# esp8266-breakout.net
KiCad netlist of a schematic drawn in EAGLE
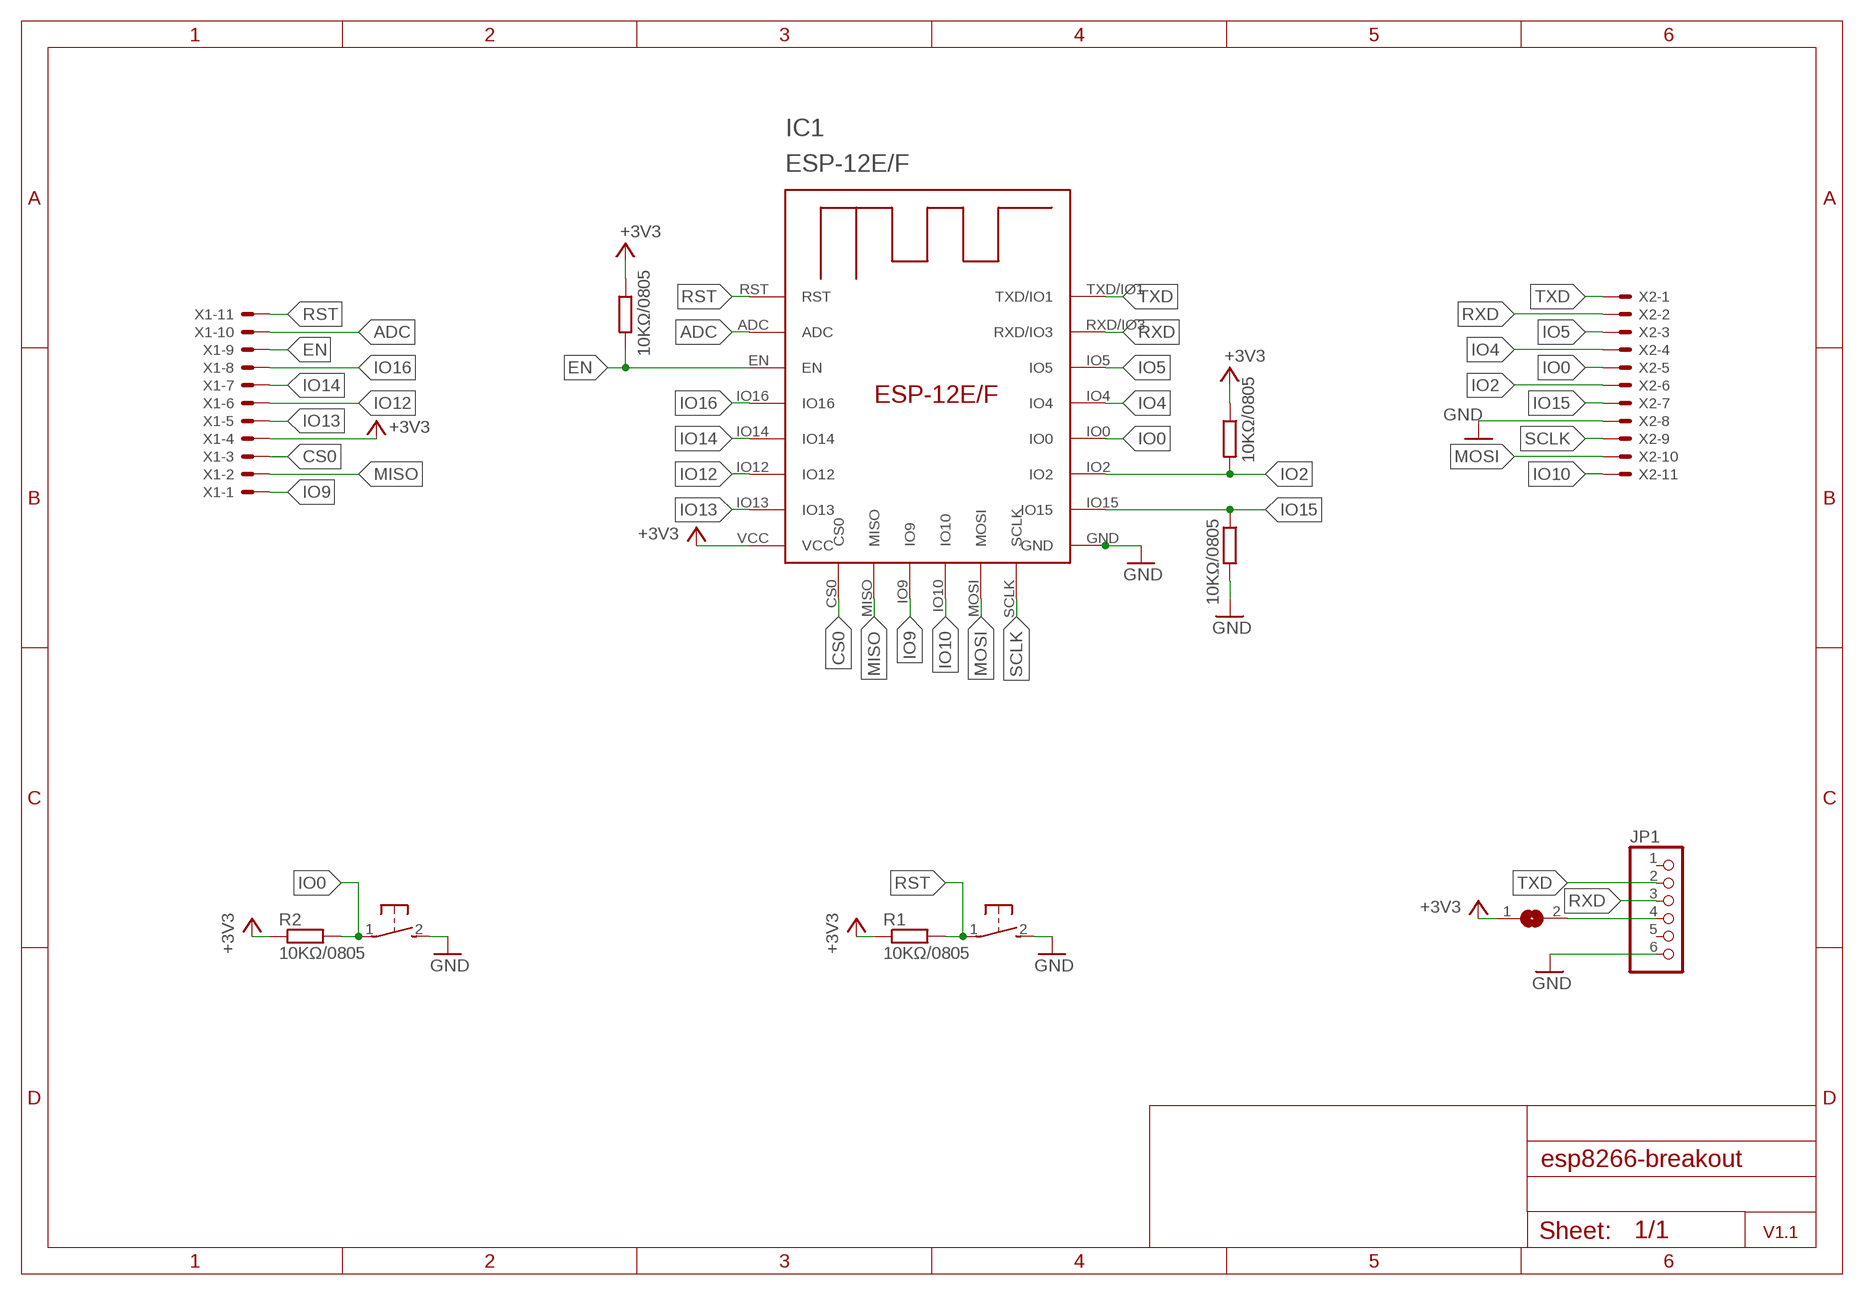
[diagram p0: schematic, sheet 1]

(export (version "E")
  (design (tool "Eeschema 10.0.6"))
  (components
    (comp (ref "IC1")
      (value "ESP-12E/F")
      (footprint "eagle-import:ESP-12E")
      (libsource (lib "eagle-import") (part "ESP-12E/F"))
    )
    (comp (ref "JP1")
      (value "PINHD-1X6B")
      (footprint "eagle-import:1X06-BIG")
      (libsource (lib "eagle-import") (part "PINHD-1X6B"))
    )
    (comp (ref "R1")
      (value "10KΩ/0805")
      (footprint "eagle-import:R0805")
      (libsource (lib "eagle-import") (part "R-EU_R0805"))
    )
    (comp (ref "R2")
      (value "10KΩ/0805")
      (footprint "eagle-import:R0805")
      (libsource (lib "eagle-import") (part "R-EU_R0805"))
    )
    (comp (ref "R3")
      (value "10KΩ/0805")
      (footprint "eagle-import:R0805")
      (libsource (lib "eagle-import") (part "R-EU_R0805"))
    )
    (comp (ref "R4")
      (value "10KΩ/0805")
      (footprint "eagle-import:R0805")
      (libsource (lib "eagle-import") (part "R-EU_R0805"))
    )
    (comp (ref "R5")
      (value "10KΩ/0805")
      (footprint "eagle-import:R0805")
      (libsource (lib "eagle-import") (part "R-EU_R0805"))
    )
    (comp (ref "S1")
      (value "DTSM-3")
      (footprint "eagle-import:DTSM-3")
      (libsource (lib "eagle-import") (part "DTSM-3"))
    )
    (comp (ref "S2")
      (value "DTSM-3")
      (footprint "eagle-import:DTSM-3")
      (libsource (lib "eagle-import") (part "DTSM-3"))
    )
    (comp (ref "SJ1") (value "SJ") (footprint "eagle-import:SJ") (libsource (lib "eagle-import") (part "SJ")))
    (comp (ref "X1")
      (value "JST-XH-11-PIN-ROUND-PAD")
      (footprint "eagle-import:JST-XH-11-PACKAGE-ROUND-PAD")
      (libsource (lib "eagle-import") (part "JST-XH-11-PIN-ROUND-PAD"))
    )
    (comp (ref "X2")
      (value "JST-XH-11-PIN-ROUND-PAD")
      (footprint "eagle-import:JST-XH-11-PACKAGE-ROUND-PAD")
      (libsource (lib "eagle-import") (part "JST-XH-11-PIN-ROUND-PAD"))
    )
  )
  (nets
    (net (code "1") (name "+3V3") (class "Default")
      (node (ref "IC1") (pin "VCC") (pinfunction "VCC_VCC") (pintype "power_in"))
      (node (ref "R1") (pin "1") (pinfunction "1_1") (pintype "passive"))
      (node (ref "R2") (pin "1") (pinfunction "1_1") (pintype "passive"))
      (node (ref "R4") (pin "1") (pinfunction "1_1") (pintype "passive"))
      (node (ref "R5") (pin "1") (pinfunction "1_1") (pintype "passive"))
      (node (ref "SJ1") (pin "1") (pinfunction "1_1") (pintype "passive"))
      (node (ref "X1") (pin "4") (pinfunction "S_4") (pintype "passive"))
    )
    (net (code "2") (name "ADC") (class "Default")
      (node (ref "IC1") (pin "ADC") (pinfunction "ADC_ADC") (pintype "bidirectional"))
      (node (ref "X1") (pin "10") (pinfunction "S_10") (pintype "passive"))
    )
    (net (code "3") (name "CS0") (class "Default")
      (node (ref "IC1") (pin "CS0") (pinfunction "CS0_CS0") (pintype "bidirectional"))
      (node (ref "X1") (pin "3") (pinfunction "S_3") (pintype "passive"))
    )
    (net (code "4") (name "EN") (class "Default")
      (node (ref "IC1") (pin "EN") (pinfunction "EN_EN") (pintype "bidirectional"))
      (node (ref "R5") (pin "2") (pinfunction "2_2") (pintype "passive"))
      (node (ref "X1") (pin "9") (pinfunction "S_9") (pintype "passive"))
    )
    (net (code "5") (name "GND") (class "Default")
      (node (ref "IC1") (pin "GND") (pinfunction "GND_GND") (pintype "power_in"))
      (node (ref "JP1") (pin "6") (pinfunction "6_6") (pintype "passive"))
      (node (ref "R3") (pin "2") (pinfunction "2_2") (pintype "passive"))
      (node (ref "S1") (pin "2") (pinfunction "2_2") (pintype "passive"))
      (node (ref "S2") (pin "2") (pinfunction "2_2") (pintype "passive"))
      (node (ref "X2") (pin "8") (pinfunction "S_8") (pintype "passive"))
    )
    (net (code "6") (name "IO0") (class "Default")
      (node (ref "IC1") (pin "IO0") (pinfunction "IO0_IO0") (pintype "bidirectional"))
      (node (ref "R2") (pin "2") (pinfunction "2_2") (pintype "passive"))
      (node (ref "S2") (pin "1") (pinfunction "1_1") (pintype "passive"))
      (node (ref "X2") (pin "5") (pinfunction "S_5") (pintype "passive"))
    )
    (net (code "7") (name "IO2") (class "Default")
      (node (ref "IC1") (pin "IO2") (pinfunction "IO2_IO2") (pintype "bidirectional"))
      (node (ref "R4") (pin "2") (pinfunction "2_2") (pintype "passive"))
      (node (ref "X2") (pin "6") (pinfunction "S_6") (pintype "passive"))
    )
    (net (code "8") (name "IO4") (class "Default")
      (node (ref "IC1") (pin "IO4") (pinfunction "IO4_IO4") (pintype "bidirectional"))
      (node (ref "X2") (pin "4") (pinfunction "S_4") (pintype "passive"))
    )
    (net (code "9") (name "IO5") (class "Default")
      (node (ref "IC1") (pin "IO5") (pinfunction "IO5_IO5") (pintype "bidirectional"))
      (node (ref "X2") (pin "3") (pinfunction "S_3") (pintype "passive"))
    )
    (net (code "10") (name "IO9") (class "Default")
      (node (ref "IC1") (pin "IO9") (pinfunction "IO9_IO9") (pintype "bidirectional"))
      (node (ref "X1") (pin "1") (pinfunction "S_1") (pintype "passive"))
    )
    (net (code "11") (name "IO10") (class "Default")
      (node (ref "IC1") (pin "IO10") (pinfunction "IO10_IO10") (pintype "bidirectional"))
      (node (ref "X2") (pin "11") (pinfunction "S_11") (pintype "passive"))
    )
    (net (code "12") (name "IO12") (class "Default")
      (node (ref "IC1") (pin "IO12") (pinfunction "IO12_IO12") (pintype "bidirectional"))
      (node (ref "X1") (pin "6") (pinfunction "S_6") (pintype "passive"))
    )
    (net (code "13") (name "IO13") (class "Default")
      (node (ref "IC1") (pin "IO13") (pinfunction "IO13_IO13") (pintype "bidirectional"))
      (node (ref "X1") (pin "5") (pinfunction "S_5") (pintype "passive"))
    )
    (net (code "14") (name "IO14") (class "Default")
      (node (ref "IC1") (pin "IO14") (pinfunction "IO14_IO14") (pintype "bidirectional"))
      (node (ref "X1") (pin "7") (pinfunction "S_7") (pintype "passive"))
    )
    (net (code "15") (name "IO15") (class "Default")
      (node (ref "IC1") (pin "IO15") (pinfunction "IO15_IO15") (pintype "bidirectional"))
      (node (ref "R3") (pin "1") (pinfunction "1_1") (pintype "passive"))
      (node (ref "X2") (pin "7") (pinfunction "S_7") (pintype "passive"))
    )
    (net (code "16") (name "IO16") (class "Default")
      (node (ref "IC1") (pin "IO16") (pinfunction "IO16_IO16") (pintype "bidirectional"))
      (node (ref "X1") (pin "8") (pinfunction "S_8") (pintype "passive"))
    )
    (net (code "17") (name "MISO") (class "Default")
      (node (ref "IC1") (pin "MISO") (pinfunction "MISO_MISO") (pintype "bidirectional"))
      (node (ref "X1") (pin "2") (pinfunction "S_2") (pintype "passive"))
    )
    (net (code "18") (name "MOSI") (class "Default")
      (node (ref "IC1") (pin "MOSI") (pinfunction "MOSI_MOSI") (pintype "bidirectional"))
      (node (ref "X2") (pin "10") (pinfunction "S_10") (pintype "passive"))
    )
    (net (code "19") (name "Net-(JP1-Pad4)") (class "Default")
      (node (ref "JP1") (pin "4") (pinfunction "4_4") (pintype "passive"))
      (node (ref "SJ1") (pin "2") (pinfunction "2_2") (pintype "passive"))
    )
    (net (code "20") (name "RST") (class "Default")
      (node (ref "IC1") (pin "RST") (pinfunction "RST_RST") (pintype "input"))
      (node (ref "R1") (pin "2") (pinfunction "2_2") (pintype "passive"))
      (node (ref "S1") (pin "1") (pinfunction "1_1") (pintype "passive"))
      (node (ref "X1") (pin "11") (pinfunction "S_11") (pintype "passive"))
    )
    (net (code "21") (name "RXD") (class "Default")
      (node (ref "IC1") (pin "RXD/IO3") (pinfunction "RXD/IO3_RXD/IO3") (pintype "bidirectional"))
      (node (ref "JP1") (pin "3") (pinfunction "3_3") (pintype "passive"))
      (node (ref "X2") (pin "2") (pinfunction "S_2") (pintype "passive"))
    )
    (net (code "22") (name "SCLK") (class "Default")
      (node (ref "IC1") (pin "SCLK") (pinfunction "SCLK_SCLK") (pintype "bidirectional"))
      (node (ref "X2") (pin "9") (pinfunction "S_9") (pintype "passive"))
    )
    (net (code "23") (name "TXD") (class "Default")
      (node (ref "IC1") (pin "TXD/IO1") (pinfunction "TXD/IO1_TXD/IO1") (pintype "bidirectional"))
      (node (ref "JP1") (pin "2") (pinfunction "2_2") (pintype "passive"))
      (node (ref "X2") (pin "1") (pinfunction "S_1") (pintype "passive"))
    )
    (net (code "24") (name "unconnected-(JP1-Pad1)") (class "Default")
      (node (ref "JP1") (pin "1") (pinfunction "1_1") (pintype "passive"))
    )
    (net (code "25") (name "unconnected-(JP1-Pad5)") (class "Default")
      (node (ref "JP1") (pin "5") (pinfunction "5_5") (pintype "passive"))
    )
  )
)
